# UVBox-I2C.net
KiCad netlist of a schematic drawn in EAGLE
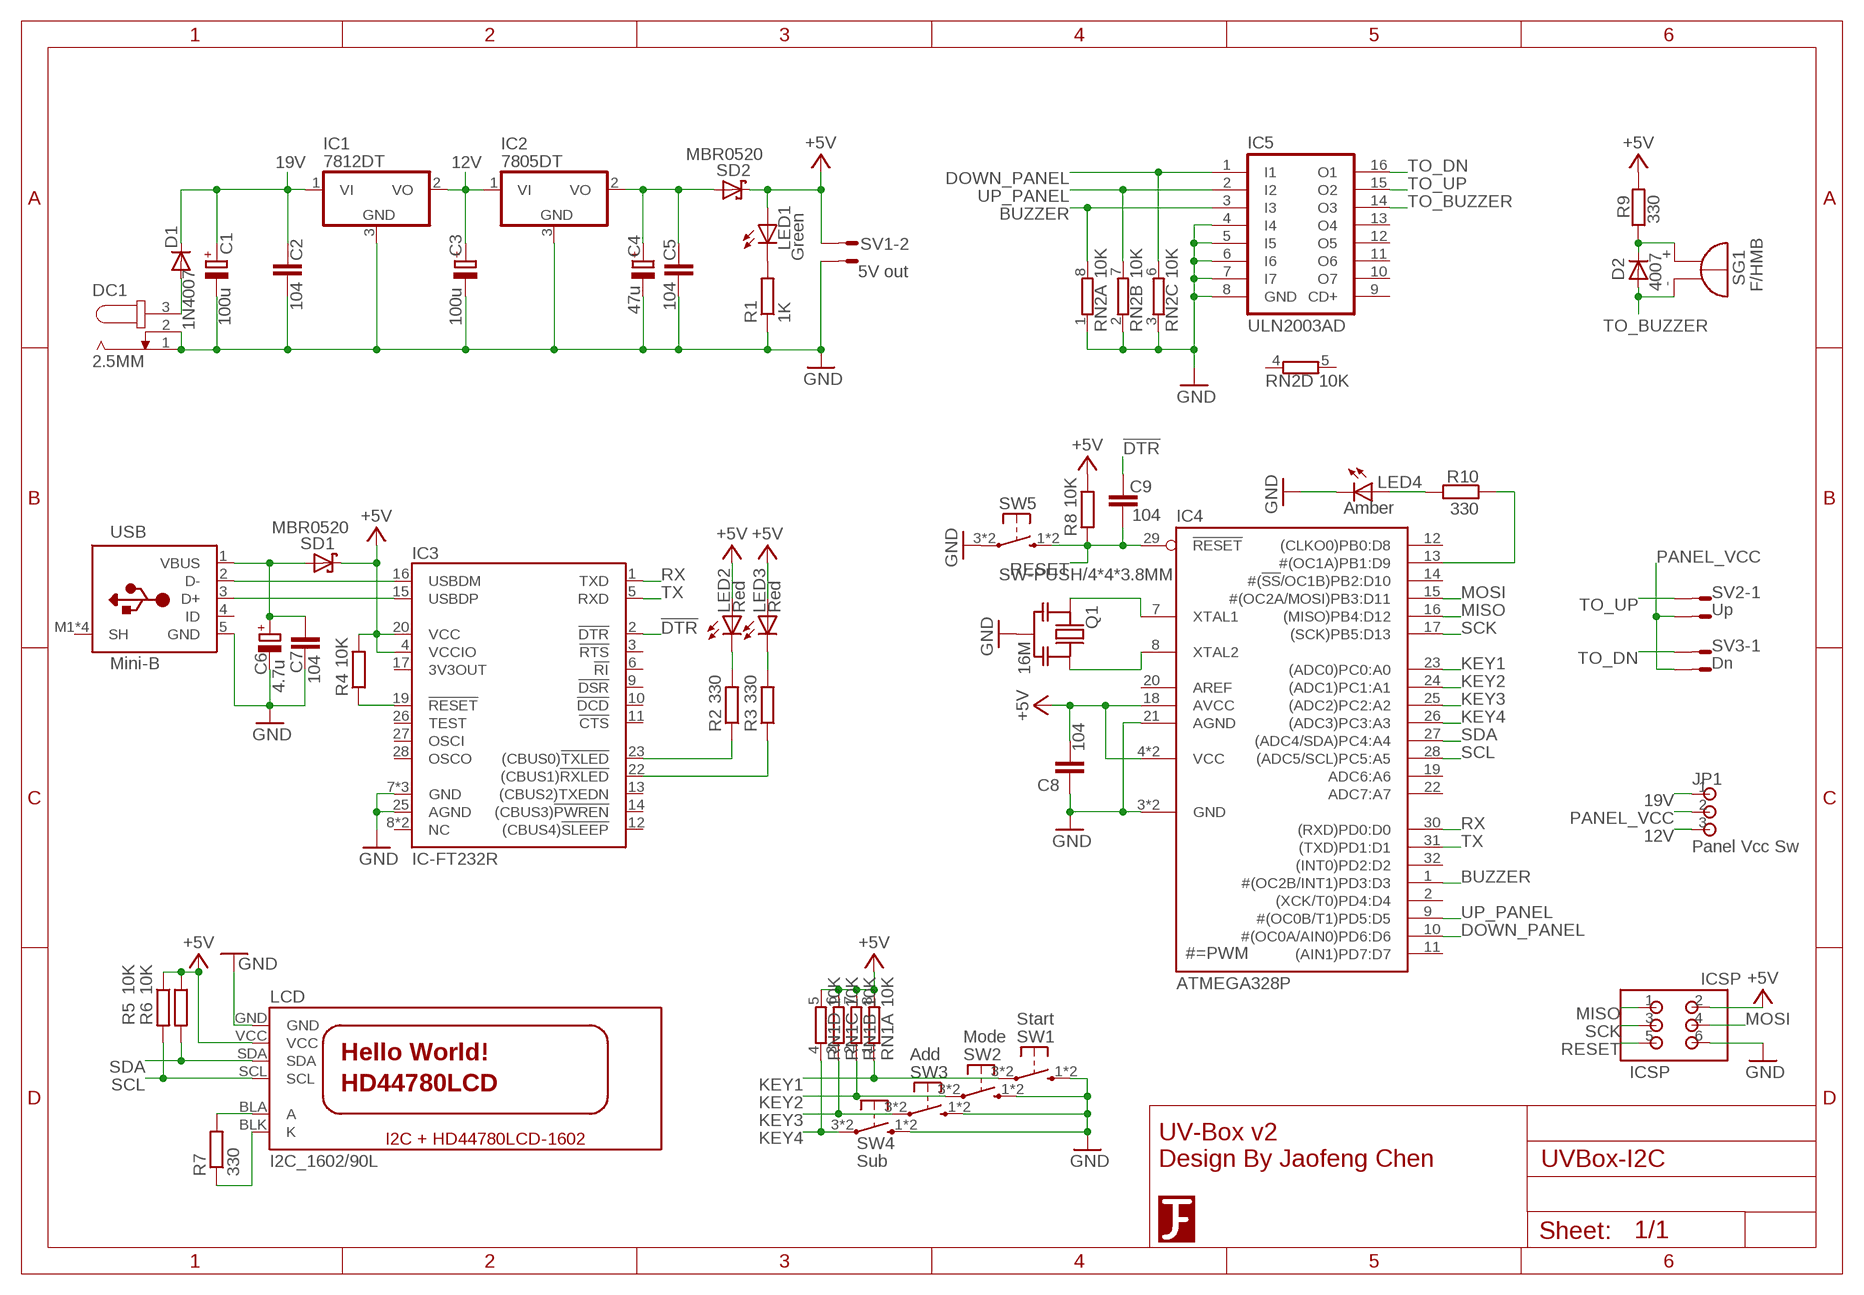
[diagram p0: schematic, sheet 1]

(export (version "E")
  (design (tool "Eeschema 10.0.6"))
  (components
    (comp (ref "C1")
      (value "100u")
      (footprint "eagle-import:140CLH-0810")
      (libsource (lib "eagle-import") (part "CPOL-EU140CLH-0810"))
    )
    (comp (ref "C2")
      (value "104")
      (footprint "eagle-import:C0805")
      (libsource (lib "eagle-import") (part "C-EUC0805"))
    )
    (comp (ref "C3")
      (value "100u")
      (footprint "eagle-import:SMC_C")
      (libsource (lib "eagle-import") (part "CPOL-EUSMCC"))
    )
    (comp (ref "C4")
      (value "47u")
      (footprint "eagle-import:SMC_C")
      (libsource (lib "eagle-import") (part "CPOL-EUSMCC"))
    )
    (comp (ref "C5")
      (value "104")
      (footprint "eagle-import:C0805")
      (libsource (lib "eagle-import") (part "C-EUC0805"))
    )
    (comp (ref "C6")
      (value "4.7u")
      (footprint "eagle-import:SMC_C")
      (libsource (lib "eagle-import") (part "CPOL-EUSMCC"))
    )
    (comp (ref "C7")
      (value "104")
      (footprint "eagle-import:C0805")
      (libsource (lib "eagle-import") (part "C-EUC0805"))
    )
    (comp (ref "C8")
      (value "104")
      (footprint "eagle-import:C0805")
      (libsource (lib "eagle-import") (part "C-EUC0805"))
    )
    (comp (ref "C9")
      (value "104")
      (footprint "eagle-import:C0805")
      (libsource (lib "eagle-import") (part "C-EUC0805"))
    )
    (comp (ref "D1")
      (value "1N4007")
      (footprint "eagle-import:DO-214AC")
      (libsource (lib "eagle-import") (part "DIODE-DO-214AC"))
    )
    (comp (ref "D2")
      (value "4007")
      (footprint "eagle-import:DO214AA")
      (libsource (lib "eagle-import") (part "DIODE-DO214AA"))
    )
    (comp (ref "DC1")
      (value "2.5MM")
      (footprint "eagle-import:SPC4078")
      (libsource (lib "eagle-import") (part "DC-JACK/2.5MM"))
    )
    (comp (ref "IC1")
      (value "7812DT")
      (footprint "eagle-import:TO252")
      (libsource (lib "eagle-import") (part "78DT12"))
    )
    (comp (ref "IC2")
      (value "7805DT")
      (footprint "eagle-import:TO252")
      (libsource (lib "eagle-import") (part "78DT05"))
    )
    (comp (ref "IC3")
      (value "IC-FT232R")
      (footprint "eagle-import:SSOP28")
      (libsource (lib "eagle-import") (part "IC-FT232R"))
    )
    (comp (ref "IC4")
      (value "ATMEGA328P")
      (footprint "eagle-import:TQFP32")
      (libsource (lib "eagle-import") (part "ATMEGA-TQFP32328P"))
    )
    (comp (ref "IC5")
      (value "ULN2003AD")
      (footprint "eagle-import:SO16")
      (libsource (lib "eagle-import") (part "ULN2003AD"))
    )
    (comp (ref "ICSP")
      (value "ICSP")
      (footprint "eagle-import:DIP-2.54-2X3")
      (libsource (lib "eagle-import") (part "PIN-2X3/2.54-DIP"))
    )
    (comp (ref "JP1")
      (value "Panel Vcc Sw")
      (footprint "eagle-import:DIP-2.0-1X3")
      (libsource (lib "eagle-import") (part "PIN-1X3-2.0"))
    )
    (comp (ref "LCD")
      (value "I2C_1602/90L")
      (footprint "eagle-import:I2C_1602_90L")
      (libsource (lib "eagle-import") (part "I2C_1602/90L"))
    )
    (comp (ref "LED1")
      (value "Green")
      (footprint "eagle-import:CHIPLED_1206")
      (libsource (lib "eagle-import") (part "LEDCHIPLED_1206"))
    )
    (comp (ref "LED2")
      (value "Red")
      (footprint "eagle-import:CHIPLED_1206")
      (libsource (lib "eagle-import") (part "LEDCHIPLED_1206"))
    )
    (comp (ref "LED3")
      (value "Red")
      (footprint "eagle-import:CHIPLED_1206")
      (libsource (lib "eagle-import") (part "LEDCHIPLED_1206"))
    )
    (comp (ref "LED4")
      (value "Amber")
      (footprint "eagle-import:CHIPLED_1206")
      (libsource (lib "eagle-import") (part "LEDCHIPLED_1206"))
    )
    (comp (ref "Q1")
      (value "16M")
      (footprint "eagle-import:CSTCE")
      (libsource (lib "eagle-import") (part "CERMOSCILL-CSTCE"))
    )
    (comp (ref "R1")
      (value "1K")
      (footprint "eagle-import:R0805")
      (libsource (lib "eagle-import") (part "R-EU_R0805"))
    )
    (comp (ref "R2")
      (value "330")
      (footprint "eagle-import:R0805")
      (libsource (lib "eagle-import") (part "R-EU_R0805"))
    )
    (comp (ref "R3")
      (value "330")
      (footprint "eagle-import:R0805")
      (libsource (lib "eagle-import") (part "R-EU_R0805"))
    )
    (comp (ref "R4")
      (value "10K")
      (footprint "eagle-import:R0805")
      (libsource (lib "eagle-import") (part "R-EU_R0805"))
    )
    (comp (ref "R5")
      (value "10K")
      (footprint "eagle-import:R0805")
      (libsource (lib "eagle-import") (part "R-EU_R0805"))
    )
    (comp (ref "R6")
      (value "10K")
      (footprint "eagle-import:R0805")
      (libsource (lib "eagle-import") (part "R-EU_R0805"))
    )
    (comp (ref "R7")
      (value "330")
      (footprint "eagle-import:R0805")
      (libsource (lib "eagle-import") (part "R-EU_R0805"))
    )
    (comp (ref "R8")
      (value "10K")
      (footprint "eagle-import:R0805")
      (libsource (lib "eagle-import") (part "R-EU_R0805"))
    )
    (comp (ref "R9")
      (value "330")
      (footprint "eagle-import:R0805")
      (libsource (lib "eagle-import") (part "R-EU_R0805"))
    )
    (comp (ref "R10")
      (value "330")
      (footprint "eagle-import:R0805")
      (libsource (lib "eagle-import") (part "R-EU_R0805"))
    )
    (comp (ref "RN1")
      (value "10K")
      (footprint "eagle-import:CAY16")
      (libsource (lib "eagle-import") (part "RN4R-CAY16"))
    )
    (comp (ref "RN2")
      (value "10K")
      (footprint "eagle-import:CAY16")
      (libsource (lib "eagle-import") (part "RN4R-CAY16"))
    )
    (comp (ref "SD1")
      (value "MBR0520")
      (footprint "eagle-import:SOD123")
      (libsource (lib "eagle-import") (part "SCHOTTKY"))
    )
    (comp (ref "SD2")
      (value "MBR0520")
      (footprint "eagle-import:SOD123")
      (libsource (lib "eagle-import") (part "SCHOTTKY"))
    )
    (comp (ref "SG1")
      (value "F/HMB")
      (footprint "eagle-import:F_HMB")
      (libsource (lib "eagle-import") (part "F/HMB"))
    )
    (comp (ref "SV1")
      (value "5V out")
      (footprint "eagle-import:L02P")
      (libsource (lib "eagle-import") (part "L02P"))
    )
    (comp (ref "SV2")
      (value "Up")
      (footprint "eagle-import:L02P")
      (libsource (lib "eagle-import") (part "L02P"))
    )
    (comp (ref "SV3")
      (value "Dn")
      (footprint "eagle-import:L02P")
      (libsource (lib "eagle-import") (part "L02P"))
    )
    (comp (ref "SW1")
      (value "Start")
      (footprint "eagle-import:SW-6_6_3.8MM")
      (libsource (lib "eagle-import") (part "SW-PUSH/663.8MM"))
    )
    (comp (ref "SW2")
      (value "Mode")
      (footprint "eagle-import:SW-6_6_3.8MM")
      (libsource (lib "eagle-import") (part "SW-PUSH/663.8MM"))
    )
    (comp (ref "SW3")
      (value "Add")
      (footprint "eagle-import:SW-6_6_3.8MM")
      (libsource (lib "eagle-import") (part "SW-PUSH/663.8MM"))
    )
    (comp (ref "SW4")
      (value "Sub")
      (footprint "eagle-import:SW-6_6_3.8MM")
      (libsource (lib "eagle-import") (part "SW-PUSH/663.8MM"))
    )
    (comp (ref "SW5")
      (value "SW-PUSH/4*4*3.8MM")
      (footprint "eagle-import:SW-4_4_3.8MM")
      (libsource (lib "eagle-import") (part "SW-PUSH/443.8MM"))
    )
    (comp (ref "U$2")
      (value "LOGO-3")
      (footprint "eagle-import:LOGO-3")
      (libsource (lib "eagle-import") (part "LOGO-3"))
    )
    (comp (ref "USB")
      (value "Mini-B")
      (footprint "eagle-import:USB-MINI-B(NO_HOLE)")
      (libsource (lib "eagle-import") (part "USB-MINI-B/NO_HOLE"))
    )
  )
  (nets
    (net (code "1") (name "+5V") (class "Default")
      (node (ref "C8") (pin "2") (pinfunction "2_2") (pintype "passive"))
      (node (ref "IC3") (pin "20") (pinfunction "VCC_20") (pintype "power_in"))
      (node (ref "IC3") (pin "4") (pinfunction "VCCIO_4") (pintype "power_in"))
      (node (ref "IC4") (pin "18") (pinfunction "AVCC_18") (pintype "passive"))
      (node (ref "IC4") (pin "4") (pinfunction "VCC_4") (pintype "power_in"))
      (node (ref "IC4") (pin "6") (pinfunction "VCC_6") (pintype "power_in"))
      (node (ref "ICSP") (pin "2") (pinfunction "2_2") (pintype "passive"))
      (node (ref "LCD") (pin "VCC") (pinfunction "VCC_VCC") (pintype "power_in"))
      (node (ref "LED1") (pin "A") (pinfunction "A_A") (pintype "passive"))
      (node (ref "LED2") (pin "A") (pinfunction "A_A") (pintype "passive"))
      (node (ref "LED3") (pin "A") (pinfunction "A_A") (pintype "passive"))
      (node (ref "R4") (pin "2") (pinfunction "2_2") (pintype "passive"))
      (node (ref "R5") (pin "1") (pinfunction "1_1") (pintype "passive"))
      (node (ref "R6") (pin "1") (pinfunction "1_1") (pintype "passive"))
      (node (ref "R8") (pin "2") (pinfunction "2_2") (pintype "passive"))
      (node (ref "R9") (pin "2") (pinfunction "2_2") (pintype "passive"))
      (node (ref "RN1") (pin "5") (pinfunction "2_5") (pintype "passive"))
      (node (ref "RN1") (pin "6") (pinfunction "2_6") (pintype "passive"))
      (node (ref "RN1") (pin "7") (pinfunction "2_7") (pintype "passive"))
      (node (ref "RN1") (pin "8") (pinfunction "2_8") (pintype "passive"))
      (node (ref "SD1") (pin "K") (pinfunction "K_K") (pintype "passive"))
      (node (ref "SD2") (pin "K") (pinfunction "K_K") (pintype "passive"))
      (node (ref "SV1") (pin "2") (pinfunction "S_2") (pintype "passive"))
    )
    (net (code "2") (name "/12V") (class "Default")
      (node (ref "C3") (pin "+") (pinfunction "+_+") (pintype "passive"))
      (node (ref "IC1") (pin "2") (pinfunction "VO_2") (pintype "passive"))
      (node (ref "IC2") (pin "1") (pinfunction "VI_1") (pintype "input"))
      (node (ref "JP1") (pin "3") (pinfunction "3_3") (pintype "passive"))
    )
    (net (code "3") (name "/19V") (class "Default")
      (node (ref "C1") (pin "+") (pinfunction "+_+") (pintype "passive"))
      (node (ref "C2") (pin "1") (pinfunction "1_1") (pintype "passive"))
      (node (ref "D1") (pin "C") (pinfunction "C_C") (pintype "passive"))
      (node (ref "IC1") (pin "1") (pinfunction "VI_1") (pintype "input"))
      (node (ref "JP1") (pin "1") (pinfunction "1_1") (pintype "passive"))
    )
    (net (code "4") (name "/BUZZER") (class "Default")
      (node (ref "IC4") (pin "1") (pinfunction "#(OC2B/INT1)PD3:D3_1") (pintype "bidirectional"))
      (node (ref "IC5") (pin "3") (pinfunction "I3_3") (pintype "input"))
      (node (ref "RN2") (pin "8") (pinfunction "2_8") (pintype "passive"))
    )
    (net (code "5") (name "/DOWN_PANEL") (class "Default")
      (node (ref "IC4") (pin "10") (pinfunction "#(OC0A/AIN0)PD6:D6_10") (pintype "bidirectional"))
      (node (ref "IC5") (pin "1") (pinfunction "I1_1") (pintype "input"))
      (node (ref "RN2") (pin "6") (pinfunction "2_6") (pintype "passive"))
    )
    (net (code "6") (name "/KEY1") (class "Default")
      (node (ref "IC4") (pin "23") (pinfunction "(ADC0)PC0:A0_23") (pintype "bidirectional"))
      (node (ref "RN1") (pin "1") (pinfunction "1_1") (pintype "passive"))
      (node (ref "SW1") (pin "3") (pinfunction "P_3") (pintype "passive"))
      (node (ref "SW1") (pin "4") (pinfunction "P_4") (pintype "passive"))
    )
    (net (code "7") (name "/KEY2") (class "Default")
      (node (ref "IC4") (pin "24") (pinfunction "(ADC1)PC1:A1_24") (pintype "bidirectional"))
      (node (ref "RN1") (pin "2") (pinfunction "1_2") (pintype "passive"))
      (node (ref "SW2") (pin "3") (pinfunction "P_3") (pintype "passive"))
      (node (ref "SW2") (pin "4") (pinfunction "P_4") (pintype "passive"))
    )
    (net (code "8") (name "/KEY3") (class "Default")
      (node (ref "IC4") (pin "25") (pinfunction "(ADC2)PC2:A2_25") (pintype "bidirectional"))
      (node (ref "RN1") (pin "3") (pinfunction "1_3") (pintype "passive"))
      (node (ref "SW3") (pin "3") (pinfunction "P_3") (pintype "passive"))
      (node (ref "SW3") (pin "4") (pinfunction "P_4") (pintype "passive"))
    )
    (net (code "9") (name "/KEY4") (class "Default")
      (node (ref "IC4") (pin "26") (pinfunction "(ADC3)PC3:A3_26") (pintype "bidirectional"))
      (node (ref "RN1") (pin "4") (pinfunction "1_4") (pintype "passive"))
      (node (ref "SW4") (pin "3") (pinfunction "P_3") (pintype "passive"))
      (node (ref "SW4") (pin "4") (pinfunction "P_4") (pintype "passive"))
    )
    (net (code "10") (name "/MISO") (class "Default")
      (node (ref "IC4") (pin "16") (pinfunction "(MISO)PB4:D12_16") (pintype "bidirectional"))
      (node (ref "ICSP") (pin "1") (pinfunction "1_1") (pintype "passive"))
    )
    (net (code "11") (name "/MOSI") (class "Default")
      (node (ref "IC4") (pin "15") (pinfunction "#(OC2A/MOSI)PB3:D11_15") (pintype "bidirectional"))
      (node (ref "ICSP") (pin "4") (pinfunction "4_4") (pintype "passive"))
    )
    (net (code "12") (name "/PANEL_VCC") (class "Default")
      (node (ref "JP1") (pin "2") (pinfunction "2_2") (pintype "passive"))
      (node (ref "SV2") (pin "2") (pinfunction "S_2") (pintype "passive"))
      (node (ref "SV3") (pin "2") (pinfunction "S_2") (pintype "passive"))
    )
    (net (code "13") (name "/RESET") (class "Default")
      (node (ref "C9") (pin "1") (pinfunction "1_1") (pintype "passive"))
      (node (ref "IC4") (pin "29") (pinfunction "~{RESET}_29") (pintype "input"))
      (node (ref "ICSP") (pin "5") (pinfunction "5_5") (pintype "passive"))
      (node (ref "R8") (pin "1") (pinfunction "1_1") (pintype "passive"))
      (node (ref "SW5") (pin "1") (pinfunction "S_1") (pintype "passive"))
      (node (ref "SW5") (pin "2") (pinfunction "S_2") (pintype "passive"))
    )
    (net (code "14") (name "/RX") (class "Default")
      (node (ref "IC3") (pin "1") (pinfunction "TXD_1") (pintype "output"))
      (node (ref "IC4") (pin "30") (pinfunction "(RXD)PD0:D0_30") (pintype "bidirectional"))
    )
    (net (code "15") (name "/SCK") (class "Default")
      (node (ref "IC4") (pin "17") (pinfunction "(SCK)PB5:D13_17") (pintype "bidirectional"))
      (node (ref "ICSP") (pin "3") (pinfunction "3_3") (pintype "passive"))
    )
    (net (code "16") (name "/SCL") (class "Default")
      (node (ref "IC4") (pin "28") (pinfunction "(ADC5/SCL)PC5:A5_28") (pintype "bidirectional"))
      (node (ref "LCD") (pin "SCL") (pinfunction "SCL_SCL") (pintype "bidirectional"))
      (node (ref "R5") (pin "2") (pinfunction "2_2") (pintype "passive"))
    )
    (net (code "17") (name "/SDA") (class "Default")
      (node (ref "IC4") (pin "27") (pinfunction "(ADC4/SDA)PC4:A4_27") (pintype "bidirectional"))
      (node (ref "LCD") (pin "SDA") (pinfunction "SDA_SDA") (pintype "bidirectional"))
      (node (ref "R6") (pin "2") (pinfunction "2_2") (pintype "passive"))
    )
    (net (code "18") (name "/TO_BUZZER") (class "Default")
      (node (ref "D2") (pin "A") (pinfunction "A_A") (pintype "passive"))
      (node (ref "IC5") (pin "14") (pinfunction "O3_14") (pintype "open_collector"))
      (node (ref "SG1") (pin "-") (pinfunction "-_-") (pintype "passive"))
    )
    (net (code "19") (name "/TO_DN") (class "Default")
      (node (ref "IC5") (pin "16") (pinfunction "O1_16") (pintype "open_collector"))
      (node (ref "SV3") (pin "1") (pinfunction "S_1") (pintype "passive"))
    )
    (net (code "20") (name "/TO_UP") (class "Default")
      (node (ref "IC5") (pin "15") (pinfunction "O2_15") (pintype "open_collector"))
      (node (ref "SV2") (pin "1") (pinfunction "S_1") (pintype "passive"))
    )
    (net (code "21") (name "/TX") (class "Default")
      (node (ref "IC3") (pin "5") (pinfunction "RXD_5") (pintype "input"))
      (node (ref "IC4") (pin "31") (pinfunction "(TXD)PD1:D1_31") (pintype "bidirectional"))
    )
    (net (code "22") (name "/UP_PANEL") (class "Default")
      (node (ref "IC4") (pin "9") (pinfunction "#(OC0B/T1)PD5:D5_9") (pintype "bidirectional"))
      (node (ref "IC5") (pin "2") (pinfunction "I2_2") (pintype "input"))
      (node (ref "RN2") (pin "7") (pinfunction "2_7") (pintype "passive"))
    )
    (net (code "23") (name "/~{DTR}") (class "Default")
      (node (ref "C9") (pin "2") (pinfunction "2_2") (pintype "passive"))
      (node (ref "IC3") (pin "2") (pinfunction "~{DTR}_2") (pintype "output"))
    )
    (net (code "24") (name "GND") (class "Default")
      (node (ref "C1") (pin "-") (pinfunction "-_-") (pintype "passive"))
      (node (ref "C2") (pin "2") (pinfunction "2_2") (pintype "passive"))
      (node (ref "C3") (pin "-") (pinfunction "-_-") (pintype "passive"))
      (node (ref "C4") (pin "-") (pinfunction "-_-") (pintype "passive"))
      (node (ref "C5") (pin "2") (pinfunction "2_2") (pintype "passive"))
      (node (ref "C6") (pin "-") (pinfunction "-_-") (pintype "passive"))
      (node (ref "C7") (pin "2") (pinfunction "2_2") (pintype "passive"))
      (node (ref "C8") (pin "1") (pinfunction "1_1") (pintype "passive"))
      (node (ref "DC1") (pin "1") (pinfunction "1_1") (pintype "passive"))
      (node (ref "DC1") (pin "2") (pinfunction "2_2") (pintype "passive"))
      (node (ref "IC1") (pin "3") (pinfunction "GND_3") (pintype "passive"))
      (node (ref "IC2") (pin "3") (pinfunction "GND_3") (pintype "passive"))
      (node (ref "IC3") (pin "18") (pinfunction "GND_18") (pintype "power_in"))
      (node (ref "IC3") (pin "21") (pinfunction "GND_21") (pintype "power_in"))
      (node (ref "IC3") (pin "25") (pinfunction "AGND_25") (pintype "power_in"))
      (node (ref "IC3") (pin "7") (pinfunction "GND_7") (pintype "power_in"))
      (node (ref "IC4") (pin "21") (pinfunction "AGND_21") (pintype "passive"))
      (node (ref "IC4") (pin "3") (pinfunction "GND_3") (pintype "power_in"))
      (node (ref "IC4") (pin "5") (pinfunction "GND_5") (pintype "power_in"))
      (node (ref "IC5") (pin "4") (pinfunction "I4_4") (pintype "input"))
      (node (ref "IC5") (pin "5") (pinfunction "I5_5") (pintype "input"))
      (node (ref "IC5") (pin "6") (pinfunction "I6_6") (pintype "input"))
      (node (ref "IC5") (pin "7") (pinfunction "I7_7") (pintype "input"))
      (node (ref "IC5") (pin "8") (pinfunction "GND_8") (pintype "power_in"))
      (node (ref "ICSP") (pin "6") (pinfunction "6_6") (pintype "passive"))
      (node (ref "LCD") (pin "GND") (pinfunction "GND_GND") (pintype "power_in"))
      (node (ref "LED4") (pin "C") (pinfunction "C_C") (pintype "passive"))
      (node (ref "Q1") (pin "2") (pinfunction "GND_2") (pintype "bidirectional"))
      (node (ref "R1") (pin "1") (pinfunction "1_1") (pintype "passive"))
      (node (ref "RN2") (pin "1") (pinfunction "1_1") (pintype "passive"))
      (node (ref "RN2") (pin "2") (pinfunction "1_2") (pintype "passive"))
      (node (ref "RN2") (pin "3") (pinfunction "1_3") (pintype "passive"))
      (node (ref "SV1") (pin "1") (pinfunction "S_1") (pintype "passive"))
      (node (ref "SW1") (pin "1") (pinfunction "S_1") (pintype "passive"))
      (node (ref "SW1") (pin "2") (pinfunction "S_2") (pintype "passive"))
      (node (ref "SW2") (pin "1") (pinfunction "S_1") (pintype "passive"))
      (node (ref "SW2") (pin "2") (pinfunction "S_2") (pintype "passive"))
      (node (ref "SW3") (pin "1") (pinfunction "S_1") (pintype "passive"))
      (node (ref "SW3") (pin "2") (pinfunction "S_2") (pintype "passive"))
      (node (ref "SW4") (pin "1") (pinfunction "S_1") (pintype "passive"))
      (node (ref "SW4") (pin "2") (pinfunction "S_2") (pintype "passive"))
      (node (ref "SW5") (pin "3") (pinfunction "P_3") (pintype "passive"))
      (node (ref "SW5") (pin "4") (pinfunction "P_4") (pintype "passive"))
      (node (ref "USB") (pin "5") (pinfunction "GND_5") (pintype "power_in"))
    )
    (net (code "25") (name "Net-(D1-PadA)") (class "Default")
      (node (ref "D1") (pin "A") (pinfunction "A_A") (pintype "passive"))
      (node (ref "DC1") (pin "3") (pinfunction "3_3") (pintype "passive"))
    )
    (net (code "26") (name "Net-(D2-PadC)") (class "Default")
      (node (ref "D2") (pin "C") (pinfunction "C_C") (pintype "passive"))
      (node (ref "R9") (pin "1") (pinfunction "1_1") (pintype "passive"))
      (node (ref "SG1") (pin "+") (pinfunction "+_+") (pintype "passive"))
    )
    (net (code "27") (name "Net-(IC2-VO)") (class "Default")
      (node (ref "C4") (pin "+") (pinfunction "+_+") (pintype "passive"))
      (node (ref "C5") (pin "1") (pinfunction "1_1") (pintype "passive"))
      (node (ref "IC2") (pin "2") (pinfunction "VO_2") (pintype "passive"))
      (node (ref "SD2") (pin "A") (pinfunction "A_A") (pintype "passive"))
    )
    (net (code "28") (name "Net-(IC3-(CBUS0)~{TXLED})") (class "Default")
      (node (ref "IC3") (pin "23") (pinfunction "(CBUS0)~{TXLED}_23") (pintype "bidirectional"))
      (node (ref "R2") (pin "1") (pinfunction "1_1") (pintype "passive"))
    )
    (net (code "29") (name "Net-(IC3-(CBUS1)~{RXLED})") (class "Default")
      (node (ref "IC3") (pin "22") (pinfunction "(CBUS1)~{RXLED}_22") (pintype "bidirectional"))
      (node (ref "R3") (pin "1") (pinfunction "1_1") (pintype "passive"))
    )
    (net (code "30") (name "Net-(IC3-USBDM)") (class "Default")
      (node (ref "IC3") (pin "16") (pinfunction "USBDM_16") (pintype "bidirectional"))
      (node (ref "USB") (pin "2") (pinfunction "D-_2") (pintype "bidirectional"))
    )
    (net (code "31") (name "Net-(IC3-USBDP)") (class "Default")
      (node (ref "IC3") (pin "15") (pinfunction "USBDP_15") (pintype "bidirectional"))
      (node (ref "USB") (pin "3") (pinfunction "D+_3") (pintype "bidirectional"))
    )
    (net (code "32") (name "Net-(IC3-~{RESET})") (class "Default")
      (node (ref "IC3") (pin "19") (pinfunction "~{RESET}_19") (pintype "input"))
      (node (ref "R4") (pin "1") (pinfunction "1_1") (pintype "passive"))
    )
    (net (code "33") (name "Net-(IC4-#(OC1A)PB1:D9)") (class "Default")
      (node (ref "IC4") (pin "13") (pinfunction "#(OC1A)PB1:D9_13") (pintype "bidirectional"))
      (node (ref "R10") (pin "1") (pinfunction "1_1") (pintype "passive"))
    )
    (net (code "34") (name "Net-(IC4-XTAL1)") (class "Default")
      (node (ref "IC4") (pin "7") (pinfunction "XTAL1_7") (pintype "bidirectional"))
      (node (ref "Q1") (pin "1") (pinfunction "IN_1") (pintype "bidirectional"))
    )
    (net (code "35") (name "Net-(IC4-XTAL2)") (class "Default")
      (node (ref "IC4") (pin "8") (pinfunction "XTAL2_8") (pintype "bidirectional"))
      (node (ref "Q1") (pin "3") (pinfunction "OUT_3") (pintype "bidirectional"))
    )
    (net (code "36") (name "Net-(LCD-A)") (class "Default")
      (node (ref "LCD") (pin "BLA") (pinfunction "A_BLA") (pintype "passive"))
      (node (ref "R7") (pin "2") (pinfunction "2_2") (pintype "passive"))
    )
    (net (code "37") (name "Net-(LCD-K)") (class "Default")
      (node (ref "LCD") (pin "BLK") (pinfunction "K_BLK") (pintype "passive"))
      (node (ref "R7") (pin "1") (pinfunction "1_1") (pintype "passive"))
    )
    (net (code "38") (name "Net-(LED1-PadC)") (class "Default")
      (node (ref "LED1") (pin "C") (pinfunction "C_C") (pintype "passive"))
      (node (ref "R1") (pin "2") (pinfunction "2_2") (pintype "passive"))
    )
    (net (code "39") (name "Net-(LED2-PadC)") (class "Default")
      (node (ref "LED2") (pin "C") (pinfunction "C_C") (pintype "passive"))
      (node (ref "R2") (pin "2") (pinfunction "2_2") (pintype "passive"))
    )
    (net (code "40") (name "Net-(LED3-PadC)") (class "Default")
      (node (ref "LED3") (pin "C") (pinfunction "C_C") (pintype "passive"))
      (node (ref "R3") (pin "2") (pinfunction "2_2") (pintype "passive"))
    )
    (net (code "41") (name "Net-(LED4-PadA)") (class "Default")
      (node (ref "LED4") (pin "A") (pinfunction "A_A") (pintype "passive"))
      (node (ref "R10") (pin "2") (pinfunction "2_2") (pintype "passive"))
    )
    (net (code "42") (name "Net-(USB-VBUS)") (class "Default")
      (node (ref "C6") (pin "+") (pinfunction "+_+") (pintype "passive"))
      (node (ref "C7") (pin "1") (pinfunction "1_1") (pintype "passive"))
      (node (ref "SD1") (pin "A") (pinfunction "A_A") (pintype "passive"))
      (node (ref "USB") (pin "1") (pinfunction "VBUS_1") (pintype "power_in"))
    )
    (net (code "43") (name "unconnected-(IC3-(CBUS2)TXEDN-Pad13)") (class "Default")
      (node (ref "IC3") (pin "13") (pinfunction "(CBUS2)TXEDN_13") (pintype "bidirectional"))
    )
    (net (code "44") (name "unconnected-(IC3-(CBUS3)~{PWREN}-Pad14)") (class "Default")
      (node (ref "IC3") (pin "14") (pinfunction "(CBUS3)~{PWREN}_14") (pintype "bidirectional"))
    )
    (net (code "45") (name "unconnected-(IC3-(CBUS4)~{SLEEP}-Pad12)") (class "Default")
      (node (ref "IC3") (pin "12") (pinfunction "(CBUS4)~{SLEEP}_12") (pintype "bidirectional"))
    )
    (net (code "46") (name "unconnected-(IC3-3V3OUT-Pad17)") (class "Default")
      (node (ref "IC3") (pin "17") (pinfunction "3V3OUT_17") (pintype "output"))
    )
    (net (code "47") (name "unconnected-(IC3-NC-Pad8)") (class "Default")
      (node (ref "IC3") (pin "8") (pinfunction "NC_8") (pintype "no_connect"))
    )
    (net (code "48") (name "unconnected-(IC3-NC-Pad24)") (class "Default")
      (node (ref "IC3") (pin "24") (pinfunction "NC_24") (pintype "no_connect"))
    )
    (net (code "49") (name "unconnected-(IC3-OSCI-Pad27)") (class "Default")
      (node (ref "IC3") (pin "27") (pinfunction "OSCI_27") (pintype "input"))
    )
    (net (code "50") (name "unconnected-(IC3-OSCO-Pad28)") (class "Default")
      (node (ref "IC3") (pin "28") (pinfunction "OSCO_28") (pintype "output"))
    )
    (net (code "51") (name "unconnected-(IC3-TEST-Pad26)") (class "Default")
      (node (ref "IC3") (pin "26") (pinfunction "TEST_26") (pintype "input"))
    )
    (net (code "52") (name "unconnected-(IC3-~{CTS}-Pad11)") (class "Default")
      (node (ref "IC3") (pin "11") (pinfunction "~{CTS}_11") (pintype "input"))
    )
    (net (code "53") (name "unconnected-(IC3-~{DCD}-Pad10)") (class "Default")
      (node (ref "IC3") (pin "10") (pinfunction "~{DCD}_10") (pintype "input"))
    )
    (net (code "54") (name "unconnected-(IC3-~{DSR}-Pad9)") (class "Default")
      (node (ref "IC3") (pin "9") (pinfunction "~{DSR}_9") (pintype "input"))
    )
    (net (code "55") (name "unconnected-(IC3-~{RI}-Pad6)") (class "Default")
      (node (ref "IC3") (pin "6") (pinfunction "~{RI}_6") (pintype "input"))
    )
    (net (code "56") (name "unconnected-(IC3-~{RTS}-Pad3)") (class "Default")
      (node (ref "IC3") (pin "3") (pinfunction "~{RTS}_3") (pintype "output"))
    )
    (net (code "57") (name "unconnected-(IC4-#(~{SS}{slash}OC1B)PB2:D10-Pad14)") (class "Default")
      (node (ref "IC4") (pin "14") (pinfunction "#(~{SS}/OC1B)PB2:D10_14") (pintype "bidirectional"))
    )
    (net (code "58") (name "unconnected-(IC4-(AIN1)PD7:D7-Pad11)") (class "Default")
      (node (ref "IC4") (pin "11") (pinfunction "(AIN1)PD7:D7_11") (pintype "bidirectional"))
    )
    (net (code "59") (name "unconnected-(IC4-(CLKO0)PB0:D8-Pad12)") (class "Default")
      (node (ref "IC4") (pin "12") (pinfunction "(CLKO0)PB0:D8_12") (pintype "bidirectional"))
    )
    (net (code "60") (name "unconnected-(IC4-(INT0)PD2:D2-Pad32)") (class "Default")
      (node (ref "IC4") (pin "32") (pinfunction "(INT0)PD2:D2_32") (pintype "bidirectional"))
    )
    (net (code "61") (name "unconnected-(IC4-(XCK{slash}T0)PD4:D4-Pad2)") (class "Default")
      (node (ref "IC4") (pin "2") (pinfunction "(XCK/T0)PD4:D4_2") (pintype "bidirectional"))
    )
    (net (code "62") (name "unconnected-(IC4-ADC6:A6-Pad19)") (class "Default")
      (node (ref "IC4") (pin "19") (pinfunction "ADC6:A6_19") (pintype "bidirectional"))
    )
    (net (code "63") (name "unconnected-(IC4-ADC7:A7-Pad22)") (class "Default")
      (node (ref "IC4") (pin "22") (pinfunction "ADC7:A7_22") (pintype "bidirectional"))
    )
    (net (code "64") (name "unconnected-(IC4-AREF-Pad20)") (class "Default")
      (node (ref "IC4") (pin "20") (pinfunction "AREF_20") (pintype "passive"))
    )
    (net (code "65") (name "unconnected-(IC5-CD+-Pad9)") (class "Default")
      (node (ref "IC5") (pin "9") (pinfunction "CD+_9") (pintype "passive"))
    )
    (net (code "66") (name "unconnected-(IC5-O4-Pad13)") (class "Default")
      (node (ref "IC5") (pin "13") (pinfunction "O4_13") (pintype "open_collector"))
    )
    (net (code "67") (name "unconnected-(IC5-O5-Pad12)") (class "Default")
      (node (ref "IC5") (pin "12") (pinfunction "O5_12") (pintype "open_collector"))
    )
    (net (code "68") (name "unconnected-(IC5-O6-Pad11)") (class "Default")
      (node (ref "IC5") (pin "11") (pinfunction "O6_11") (pintype "open_collector"))
    )
    (net (code "69") (name "unconnected-(IC5-O7-Pad10)") (class "Default")
      (node (ref "IC5") (pin "10") (pinfunction "O7_10") (pintype "open_collector"))
    )
    (net (code "70") (name "unconnected-(RN2D-1-Pad4)") (class "Default")
      (node (ref "RN2") (pin "4") (pinfunction "1_4") (pintype "passive"))
    )
    (net (code "71") (name "unconnected-(RN2D-2-Pad5)") (class "Default")
      (node (ref "RN2") (pin "5") (pinfunction "2_5") (pintype "passive"))
    )
    (net (code "72") (name "unconnected-(USB-ID-Pad4)") (class "Default")
      (node (ref "USB") (pin "4") (pinfunction "ID_4") (pintype "bidirectional"))
    )
    (net (code "73") (name "unconnected-(USB-SH-PadM1)") (class "Default")
      (node (ref "USB") (pin "M1") (pinfunction "SH_M1") (pintype "no_connect"))
    )
    (net (code "74") (name "unconnected-(USB-SH-PadM2)") (class "Default")
      (node (ref "USB") (pin "M2") (pinfunction "SH_M2") (pintype "no_connect"))
    )
    (net (code "75") (name "unconnected-(USB-SH-PadM3)") (class "Default")
      (node (ref "USB") (pin "M3") (pinfunction "SH_M3") (pintype "no_connect"))
    )
    (net (code "76") (name "unconnected-(USB-SH-PadM4)") (class "Default")
      (node (ref "USB") (pin "M4") (pinfunction "SH_M4") (pintype "no_connect"))
    )
  )
)
